# SOLENOID.net
KiCad netlist of a schematic drawn in Altium Designer
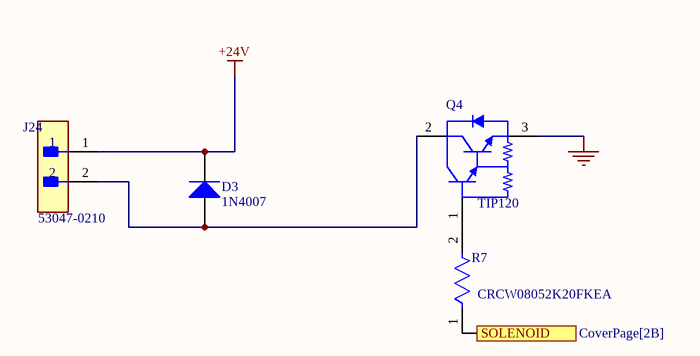
[diagram p0: SOLENOID.SchDoc]

(export (version "E")
  (design (tool "Eeschema 10.0.6"))
  (components
    (comp (ref "D3")
      (value "1N4007")
      (footprint "FAIR-DO-41-2")
      (description "General Purpose Rectifier, 1.1 V, 1.0 A, -55 to 175 degC, 2-Pin DO-41, RoHS, Tape and Reel")
      (fields (field (name "MANUFACTURER") "Fairchild"))
      (libsource (lib "Northeastern University - Generate") (part "KESE-D_K1A2-2"))
    )
    (comp (ref "J24")
      (value "53047-0210")
      (footprint "FP-53047-0210-MFG")
      (description "CONN HEADER VERT 2POS 1.25MM")
      (fields
        (field (name "OCTOPART") "https://octopart.com/53047-0210-molex-276772")
        (field (name "MANUFACTURER") "Molex")
      )
      (libsource (lib "Altium Content Vault") (part "3bc925449376181038e59eaffc5286c"))
    )
    (comp (ref "Q4")
      (value "TIP120")
      (footprint "ONSC-TO-220-3-221A-09")
      (fields (field (name "MANUFACTURER") "ON Semiconductor"))
      (libsource (lib "Northeastern University - Generate") (part "ONSC-DT-NPN-B1C2E3-3_A"))
    )
    (comp (ref "R7")
      (value "CRCW08052K20FKEA")
      (footprint "FP-CRCW0805-e3-IPC_B")
      (description "RES Thick Film, 2.2kΩ, 1%, 0.125W, 100ppm/°C, 0805")
      (fields (field (name "TOLERANCE") "1%"))
      (libsource (lib "Altium Content Vault") (part "1029c3af85768c4190bb7ad29bc67b5"))
    )
  )
  (nets
    (net (code "1") (name "+24V") (class "Default")
      (node (ref "D3") (pin "1") (pinfunction "K_1") (pintype "passive"))
      (node (ref "J24") (pin "1") (pinfunction "1_1") (pintype "passive"))
    )
    (net (code "2") (name "/SOLENOID") (class "Default")
      (node (ref "R7") (pin "1") (pinfunction "1_1") (pintype "passive"))
    )
    (net (code "3") (name "GND") (class "Default")
      (node (ref "Q4") (pin "3") (pinfunction "E_3") (pintype "passive"))
    )
    (net (code "4") (name "Net-(D3-A)") (class "Default")
      (node (ref "D3") (pin "2") (pinfunction "A_2") (pintype "passive"))
      (node (ref "J24") (pin "2") (pinfunction "2_2") (pintype "passive"))
      (node (ref "Q4") (pin "2") (pinfunction "C_2") (pintype "passive"))
    )
    (net (code "5") (name "Net-(Q4-B)") (class "Default")
      (node (ref "Q4") (pin "1") (pinfunction "B_1") (pintype "passive"))
      (node (ref "R7") (pin "2") (pinfunction "2_2") (pintype "passive"))
    )
  )
)
